# nevjegykartya2019.net
KiCad netlist of a schematic drawn in EAGLE
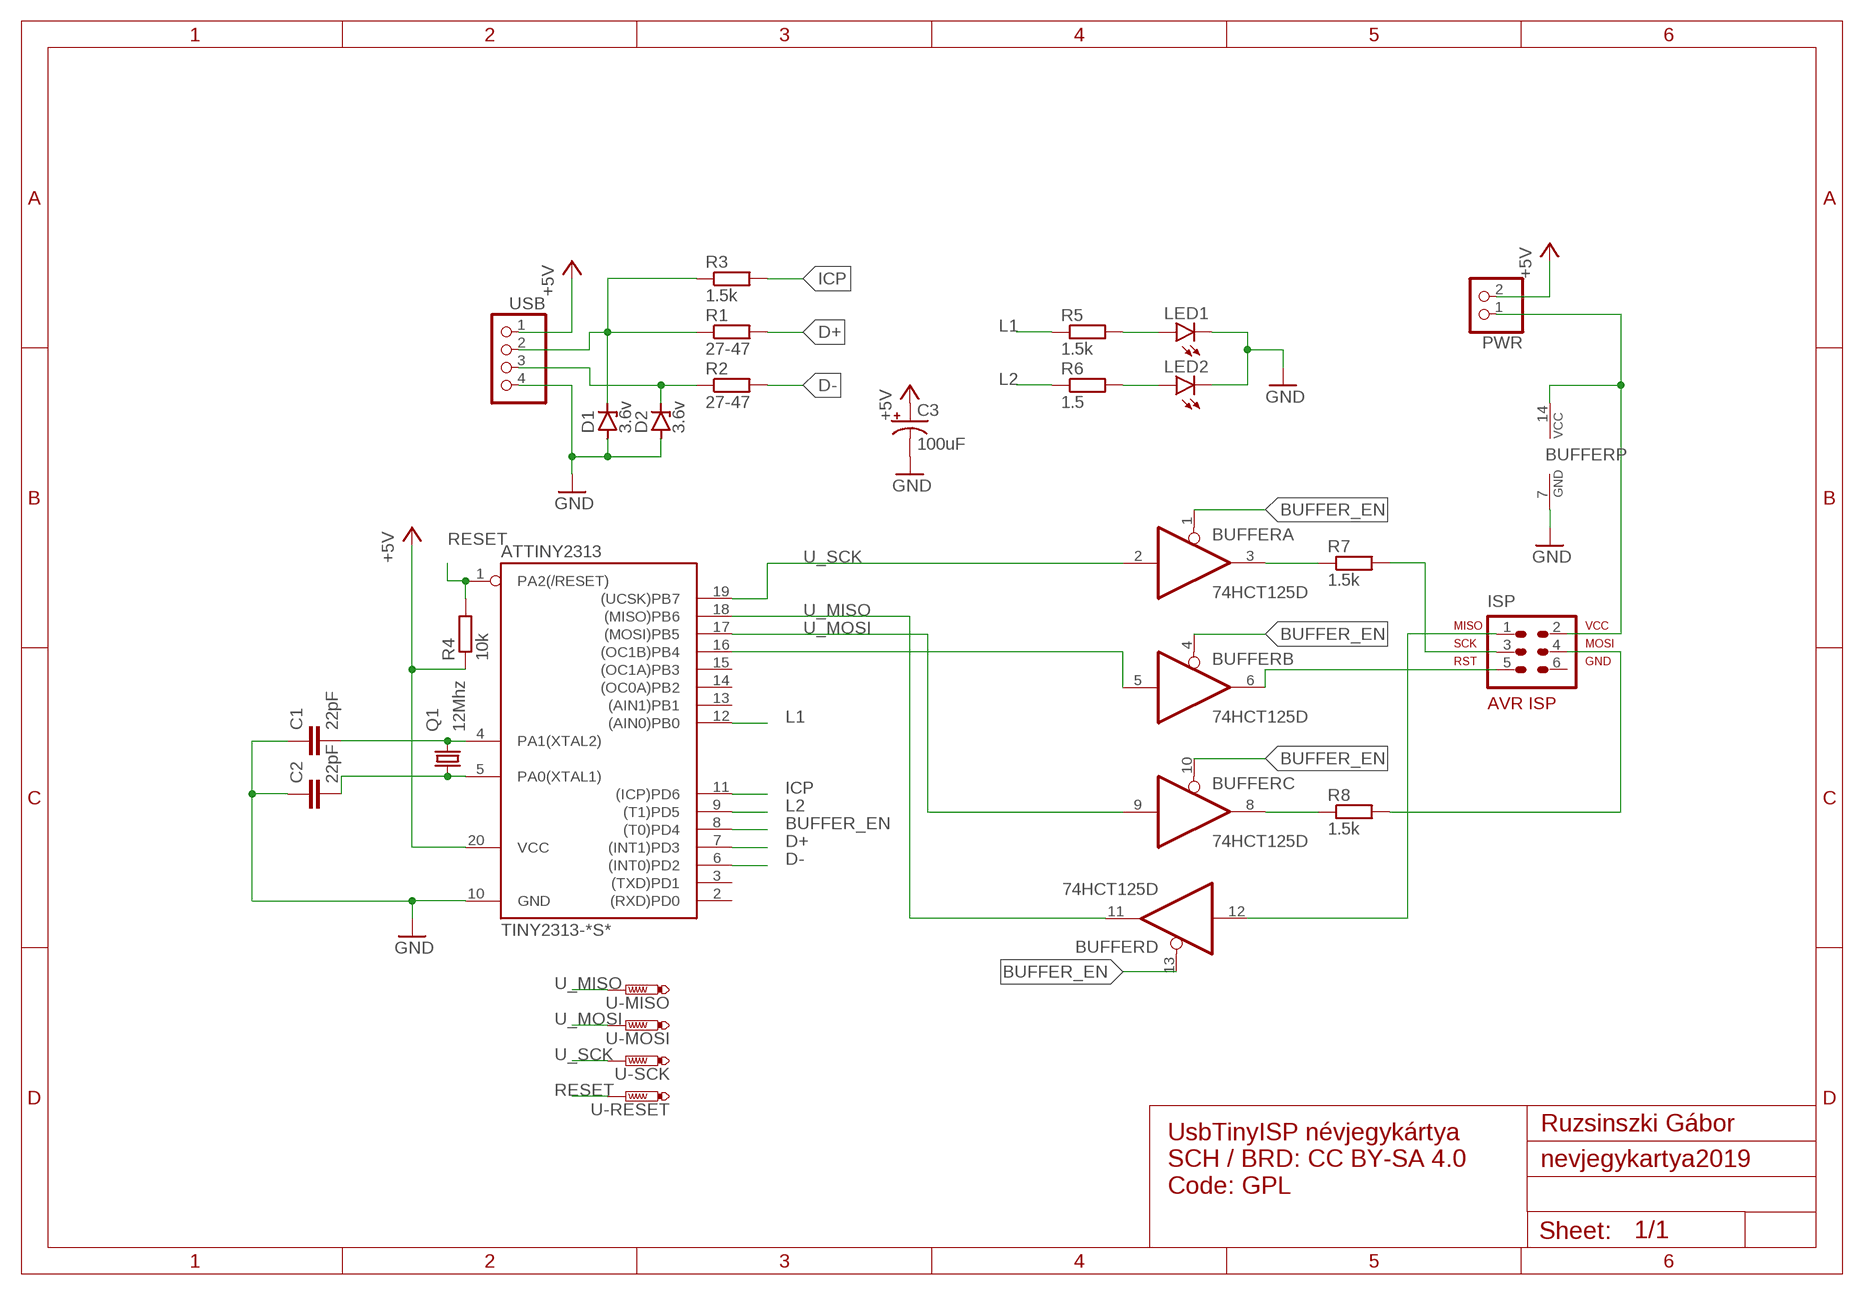
[diagram p0: schematic, sheet 1]

(export (version "E")
  (design (tool "Eeschema 10.0.6"))
  (components
    (comp (ref "ATTINY2313")
      (value "TINY2313-*S*")
      (footprint "eagle-import:SO20L$")
      (libsource (lib "eagle-import") (part "TINY2313-S"))
    )
    (comp (ref "BUFFER")
      (value "74HCT125D")
      (footprint "eagle-import:SO14")
      (libsource (lib "eagle-import") (part "74125DHCT"))
    )
    (comp (ref "C1")
      (value "22pF")
      (footprint "eagle-import:C1206")
      (libsource (lib "eagle-import") (part "C-EUC1206"))
    )
    (comp (ref "C2")
      (value "22pF")
      (footprint "eagle-import:C1206")
      (libsource (lib "eagle-import") (part "C-EUC1206"))
    )
    (comp (ref "C3")
      (value "100uF")
      (footprint "eagle-import:E2,5-5")
      (libsource (lib "eagle-import") (part "CPOL-USE2.5-5"))
    )
    (comp (ref "D1")
      (value "3.6v")
      (footprint "eagle-import:SOT223")
      (libsource (lib "eagle-import") (part "ZENER-DIODESOT223"))
    )
    (comp (ref "D2")
      (value "3.6v")
      (footprint "eagle-import:SOT223")
      (libsource (lib "eagle-import") (part "ZENER-DIODESOT223"))
    )
    (comp (ref "ISP")
      (value "AVR-ISP-6VERT")
      (footprint "eagle-import:AVR-ISP-6")
      (libsource (lib "eagle-import") (part "AVR-ISP-6VERT"))
    )
    (comp (ref "LED1")
      (value "LEDCHIPLED_1206")
      (footprint "eagle-import:CHIPLED_1206")
      (libsource (lib "eagle-import") (part "LEDCHIPLED_1206"))
    )
    (comp (ref "LED2")
      (value "LEDCHIPLED_1206")
      (footprint "eagle-import:CHIPLED_1206")
      (libsource (lib "eagle-import") (part "LEDCHIPLED_1206"))
    )
    (comp (ref "PWR")
      (value "PINHD-1X2/90")
      (footprint "eagle-import:1X02_90")
      (libsource (lib "eagle-import") (part "PINHD-1X2/90"))
    )
    (comp (ref "Q1")
      (value "12Mhz")
      (footprint "eagle-import:6.0X3.5_2")
      (libsource (lib "eagle-import") (part "KX-12B"))
    )
    (comp (ref "R1")
      (value "27-47")
      (footprint "eagle-import:M1206")
      (libsource (lib "eagle-import") (part "R-EU_M1206"))
    )
    (comp (ref "R2")
      (value "27-47")
      (footprint "eagle-import:M1206")
      (libsource (lib "eagle-import") (part "R-EU_M1206"))
    )
    (comp (ref "R3")
      (value "1.5k")
      (footprint "eagle-import:M1206")
      (libsource (lib "eagle-import") (part "R-EU_M1206"))
    )
    (comp (ref "R4")
      (value "10k")
      (footprint "eagle-import:M1206")
      (libsource (lib "eagle-import") (part "R-EU_M1206"))
    )
    (comp (ref "R5")
      (value "1.5k")
      (footprint "eagle-import:M1206")
      (libsource (lib "eagle-import") (part "R-EU_M1206"))
    )
    (comp (ref "R6")
      (value "1.5")
      (footprint "eagle-import:M1206")
      (libsource (lib "eagle-import") (part "R-EU_M1206"))
    )
    (comp (ref "R7")
      (value "1.5k")
      (footprint "eagle-import:M1206")
      (libsource (lib "eagle-import") (part "R-EU_M1206"))
    )
    (comp (ref "R8")
      (value "1.5k")
      (footprint "eagle-import:M1206")
      (libsource (lib "eagle-import") (part "R-EU_M1206"))
    )
    (comp (ref "U-MISO")
      (value "PTR1TP20SQ")
      (footprint "eagle-import:TP20SQ")
      (libsource (lib "eagle-import") (part "PTR1TP20SQ"))
    )
    (comp (ref "U-MOSI")
      (value "PTR1TP20SQ")
      (footprint "eagle-import:TP20SQ")
      (libsource (lib "eagle-import") (part "PTR1TP20SQ"))
    )
    (comp (ref "U-RESET")
      (value "PTR1TP20SQ")
      (footprint "eagle-import:TP20SQ")
      (libsource (lib "eagle-import") (part "PTR1TP20SQ"))
    )
    (comp (ref "U-SCK")
      (value "PTR1TP20SQ")
      (footprint "eagle-import:TP20SQ")
      (libsource (lib "eagle-import") (part "PTR1TP20SQ"))
    )
    (comp (ref "USB")
      (value "PINHD-1X4/90")
      (footprint "eagle-import:1X04_90")
      (libsource (lib "eagle-import") (part "PINHD-1X4/90"))
    )
  )
  (nets
    (net (code "1") (name "+5V") (class "Default")
      (node (ref "ATTINY2313") (pin "20") (pinfunction "VCC_20") (pintype "power_in"))
      (node (ref "C3") (pin "+") (pinfunction "+_+") (pintype "passive"))
      (node (ref "PWR") (pin "2") (pinfunction "2_2") (pintype "passive"))
      (node (ref "R4") (pin "1") (pinfunction "1_1") (pintype "passive"))
      (node (ref "USB") (pin "1") (pinfunction "1_1") (pintype "passive"))
    )
    (net (code "2") (name "/L1") (class "Default")
      (node (ref "ATTINY2313") (pin "12") (pinfunction "(AIN0)PB0_12") (pintype "bidirectional"))
      (node (ref "R5") (pin "1") (pinfunction "1_1") (pintype "passive"))
    )
    (net (code "3") (name "/L2") (class "Default")
      (node (ref "ATTINY2313") (pin "9") (pinfunction "(T1)PD5_9") (pintype "bidirectional"))
      (node (ref "R6") (pin "1") (pinfunction "1_1") (pintype "passive"))
    )
    (net (code "4") (name "/RESET") (class "Default")
      (node (ref "ATTINY2313") (pin "1") (pinfunction "PA2(/RESET)_1") (pintype "input"))
      (node (ref "R4") (pin "2") (pinfunction "2_2") (pintype "passive"))
      (node (ref "U-RESET") (pin "TP") (pinfunction "TP_TP") (pintype "input"))
    )
    (net (code "5") (name "/U_MISO") (class "Default")
      (node (ref "ATTINY2313") (pin "18") (pinfunction "(MISO)PB6_18") (pintype "bidirectional"))
      (node (ref "BUFFER") (pin "11") (pinfunction "O_11") (pintype "tri_state"))
      (node (ref "U-MISO") (pin "TP") (pinfunction "TP_TP") (pintype "input"))
    )
    (net (code "6") (name "/U_MOSI") (class "Default")
      (node (ref "ATTINY2313") (pin "17") (pinfunction "(MOSI)PB5_17") (pintype "bidirectional"))
      (node (ref "BUFFER") (pin "9") (pinfunction "I_9") (pintype "input"))
      (node (ref "U-MOSI") (pin "TP") (pinfunction "TP_TP") (pintype "input"))
    )
    (net (code "7") (name "/U_SCK") (class "Default")
      (node (ref "ATTINY2313") (pin "19") (pinfunction "(UCSK)PB7_19") (pintype "bidirectional"))
      (node (ref "BUFFER") (pin "2") (pinfunction "I_2") (pintype "input"))
      (node (ref "U-SCK") (pin "TP") (pinfunction "TP_TP") (pintype "input"))
    )
    (net (code "8") (name "BUFFER_EN") (class "Default")
      (node (ref "ATTINY2313") (pin "8") (pinfunction "(T0)PD4_8") (pintype "bidirectional"))
      (node (ref "BUFFER") (pin "1") (pinfunction "OE_1") (pintype "input"))
      (node (ref "BUFFER") (pin "10") (pinfunction "OE_10") (pintype "input"))
      (node (ref "BUFFER") (pin "13") (pinfunction "OE_13") (pintype "input"))
      (node (ref "BUFFER") (pin "4") (pinfunction "OE_4") (pintype "input"))
    )
    (net (code "9") (name "D+") (class "Default")
      (node (ref "ATTINY2313") (pin "7") (pinfunction "(INT1)PD3_7") (pintype "bidirectional"))
      (node (ref "R1") (pin "2") (pinfunction "2_2") (pintype "passive"))
    )
    (net (code "10") (name "D-") (class "Default")
      (node (ref "ATTINY2313") (pin "6") (pinfunction "(INT0)PD2_6") (pintype "bidirectional"))
      (node (ref "R2") (pin "2") (pinfunction "2_2") (pintype "passive"))
    )
    (net (code "11") (name "GND") (class "Default")
      (node (ref "ATTINY2313") (pin "10") (pinfunction "GND_10") (pintype "power_in"))
      (node (ref "BUFFER") (pin "7") (pinfunction "GND_7") (pintype "power_in"))
      (node (ref "C1") (pin "1") (pinfunction "1_1") (pintype "passive"))
      (node (ref "C2") (pin "1") (pinfunction "1_1") (pintype "passive"))
      (node (ref "C3") (pin "-") (pinfunction "-_-") (pintype "passive"))
      (node (ref "D1") (pin "1") (pinfunction "A_1") (pintype "passive"))
      (node (ref "D2") (pin "1") (pinfunction "A_1") (pintype "passive"))
      (node (ref "LED1") (pin "C") (pinfunction "C_C") (pintype "passive"))
      (node (ref "LED2") (pin "C") (pinfunction "C_C") (pintype "passive"))
      (node (ref "USB") (pin "4") (pinfunction "4_4") (pintype "passive"))
    )
    (net (code "12") (name "ICP") (class "Default")
      (node (ref "ATTINY2313") (pin "11") (pinfunction "(ICP)PD6_11") (pintype "bidirectional"))
      (node (ref "R3") (pin "2") (pinfunction "2_2") (pintype "passive"))
    )
    (net (code "13") (name "Net-(ATTINY2313-(OC1B)PB4)") (class "Default")
      (node (ref "ATTINY2313") (pin "16") (pinfunction "(OC1B)PB4_16") (pintype "bidirectional"))
      (node (ref "BUFFER") (pin "5") (pinfunction "I_5") (pintype "input"))
    )
    (net (code "14") (name "Net-(ATTINY2313-PA0(XTAL1))") (class "Default")
      (node (ref "ATTINY2313") (pin "5") (pinfunction "PA0(XTAL1)_5") (pintype "bidirectional"))
      (node (ref "C2") (pin "2") (pinfunction "2_2") (pintype "passive"))
      (node (ref "Q1") (pin "1") (pinfunction "1_1") (pintype "passive"))
    )
    (net (code "15") (name "Net-(ATTINY2313-PA1(XTAL2))") (class "Default")
      (node (ref "ATTINY2313") (pin "4") (pinfunction "PA1(XTAL2)_4") (pintype "bidirectional"))
      (node (ref "C1") (pin "2") (pinfunction "2_2") (pintype "passive"))
      (node (ref "Q1") (pin "2") (pinfunction "2_2") (pintype "passive"))
    )
    (net (code "16") (name "Net-(BUFFERA-O)") (class "Default")
      (node (ref "BUFFER") (pin "3") (pinfunction "O_3") (pintype "tri_state"))
      (node (ref "R7") (pin "1") (pinfunction "1_1") (pintype "passive"))
    )
    (net (code "17") (name "Net-(BUFFERB-O)") (class "Default")
      (node (ref "BUFFER") (pin "6") (pinfunction "O_6") (pintype "tri_state"))
      (node (ref "ISP") (pin "5") (pinfunction "5_5") (pintype "passive"))
    )
    (net (code "18") (name "Net-(BUFFERC-O)") (class "Default")
      (node (ref "BUFFER") (pin "8") (pinfunction "O_8") (pintype "tri_state"))
      (node (ref "R8") (pin "1") (pinfunction "1_1") (pintype "passive"))
    )
    (net (code "19") (name "Net-(BUFFERD-I)") (class "Default")
      (node (ref "BUFFER") (pin "12") (pinfunction "I_12") (pintype "input"))
      (node (ref "ISP") (pin "1") (pinfunction "1_1") (pintype "passive"))
    )
    (net (code "20") (name "Net-(BUFFERE-VCC)") (class "Default")
      (node (ref "BUFFER") (pin "14") (pinfunction "VCC_14") (pintype "power_in"))
      (node (ref "ISP") (pin "2") (pinfunction "2_2") (pintype "passive"))
      (node (ref "PWR") (pin "1") (pinfunction "1_1") (pintype "passive"))
    )
    (net (code "21") (name "Net-(D1-C)") (class "Default")
      (node (ref "D1") (pin "4") (pinfunction "C_4") (pintype "passive"))
      (node (ref "R1") (pin "1") (pinfunction "1_1") (pintype "passive"))
      (node (ref "R3") (pin "1") (pinfunction "1_1") (pintype "passive"))
      (node (ref "USB") (pin "2") (pinfunction "2_2") (pintype "passive"))
    )
    (net (code "22") (name "Net-(D2-C)") (class "Default")
      (node (ref "D2") (pin "4") (pinfunction "C_4") (pintype "passive"))
      (node (ref "R2") (pin "1") (pinfunction "1_1") (pintype "passive"))
      (node (ref "USB") (pin "3") (pinfunction "3_3") (pintype "passive"))
    )
    (net (code "23") (name "Net-(ISP-Pad3)") (class "Default")
      (node (ref "ISP") (pin "3") (pinfunction "3_3") (pintype "passive"))
      (node (ref "R7") (pin "2") (pinfunction "2_2") (pintype "passive"))
    )
    (net (code "24") (name "Net-(ISP-Pad4)") (class "Default")
      (node (ref "ISP") (pin "4") (pinfunction "4_4") (pintype "passive"))
      (node (ref "R8") (pin "2") (pinfunction "2_2") (pintype "passive"))
    )
    (net (code "25") (name "Net-(LED1-PadA)") (class "Default")
      (node (ref "LED1") (pin "A") (pinfunction "A_A") (pintype "passive"))
      (node (ref "R5") (pin "2") (pinfunction "2_2") (pintype "passive"))
    )
    (net (code "26") (name "Net-(LED2-PadA)") (class "Default")
      (node (ref "LED2") (pin "A") (pinfunction "A_A") (pintype "passive"))
      (node (ref "R6") (pin "2") (pinfunction "2_2") (pintype "passive"))
    )
    (net (code "27") (name "unconnected-(ATTINY2313-(AIN1)PB1-Pad13)") (class "Default")
      (node (ref "ATTINY2313") (pin "13") (pinfunction "(AIN1)PB1_13") (pintype "bidirectional"))
    )
    (net (code "28") (name "unconnected-(ATTINY2313-(OC0A)PB2-Pad14)") (class "Default")
      (node (ref "ATTINY2313") (pin "14") (pinfunction "(OC0A)PB2_14") (pintype "bidirectional"))
    )
    (net (code "29") (name "unconnected-(ATTINY2313-(OC1A)PB3-Pad15)") (class "Default")
      (node (ref "ATTINY2313") (pin "15") (pinfunction "(OC1A)PB3_15") (pintype "bidirectional"))
    )
    (net (code "30") (name "unconnected-(ATTINY2313-(RXD)PD0-Pad2)") (class "Default")
      (node (ref "ATTINY2313") (pin "2") (pinfunction "(RXD)PD0_2") (pintype "bidirectional"))
    )
    (net (code "31") (name "unconnected-(ATTINY2313-(TXD)PD1-Pad3)") (class "Default")
      (node (ref "ATTINY2313") (pin "3") (pinfunction "(TXD)PD1_3") (pintype "bidirectional"))
    )
    (net (code "32") (name "unconnected-(ISP-Pad6)") (class "Default")
      (node (ref "ISP") (pin "6") (pinfunction "6_6") (pintype "passive"))
    )
  )
)
